# Temperature_monitoring.net
KiCad netlist of a schematic drawn in Altium Designer
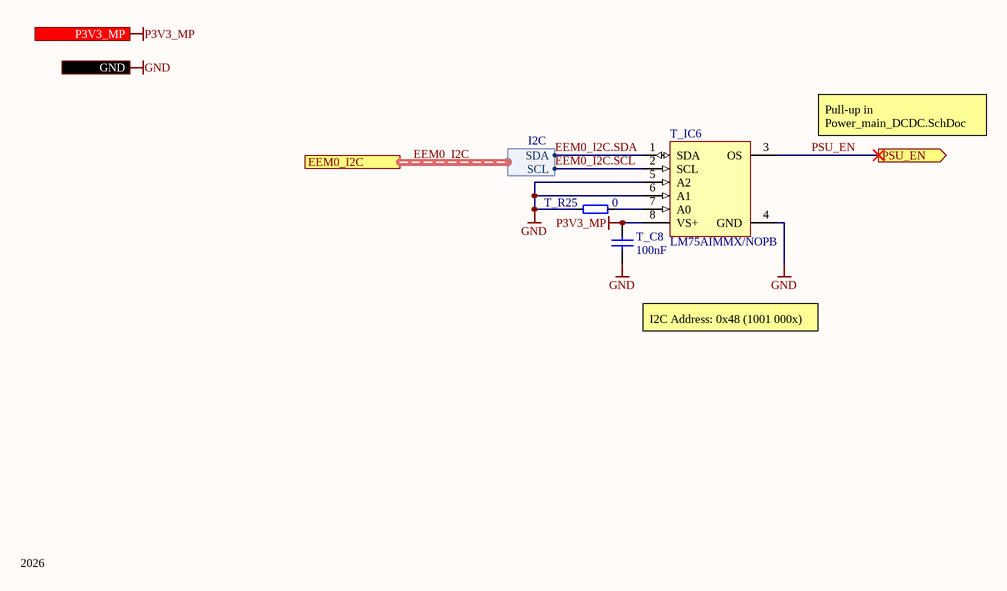
[diagram p0: Temperature_monitoring.SchDoc]

(export (version "E")
  (design (tool "Eeschema 10.0.6"))
  (components
    (comp (ref "T_C8")
      (value "100nF")
      (footprint "CAPC1005X55N")
      (description "Non-polarised capacitor")
      (fields
        (field (name "PART NUMBER") "CC0402_100NF_16V_10%_X5R")
        (field (name "VOLTAGE") "16V")
        (field (name "AUTHOR") "CERN DEM JLC")
      )
      (libsource (lib "Capacitors") (part "Capacitor - non polarized"))
    )
    (comp (ref "T_IC6")
      (value "LM75AIMMX/NOPB")
      (footprint "DGK0008A_M")
      (description "Serial Switch/Digital Sensor, 9 Bit(s), 3Cel, Square, 8 Pin, Surface Mount")
      (libsource (lib "TechnoSystem Workspace") (part "SEN-TEMP-LM75-8"))
    )
    (comp (ref "T_R25")
      (value "0")
      (footprint "RESC1005X40N")
      (description "Resistor")
      (fields
        (field (name "PART NUMBER") "R0402_0R_JUMPER")
        (field (name "MANUFACTURER") "GENERIC")
        (field (name "AUTHOR") "CERN DEM JLC")
      )
      (libsource (lib "Resistors") (part "Resistor"))
    )
  )
  (nets
    (net (code "2") (name "/EEM0_I2C.SCL") (class "Default")
      (node (ref "T_IC6") (pin "2") (pinfunction "SCL_2") (pintype "input"))
    )
    (net (code "3") (name "/EEM0_I2C.SDA") (class "Default")
      (node (ref "T_IC6") (pin "1") (pinfunction "SDA_1") (pintype "bidirectional"))
    )
    (net (code "5") (name "/PSU_EN") (class "Default")
      (node (ref "T_IC6") (pin "3") (pinfunction "OS_3") (pintype "open_collector+no_connect"))
    )
    (net (code "6") (name "GND") (class "Default")
      (node (ref "T_C8") (pin "1") (pinfunction "1_1") (pintype "passive"))
      (node (ref "T_IC6") (pin "4") (pinfunction "GND_4") (pintype "power_in"))
      (node (ref "T_IC6") (pin "5") (pinfunction "A2_5") (pintype "input"))
      (node (ref "T_IC6") (pin "6") (pinfunction "A1_6") (pintype "input"))
      (node (ref "T_R25") (pin "1") (pinfunction "1_1") (pintype "passive"))
    )
    (net (code "7") (name "Net-(T_IC6-A0)") (class "Default")
      (node (ref "T_IC6") (pin "7") (pinfunction "A0_7") (pintype "input"))
      (node (ref "T_R25") (pin "2") (pinfunction "2_2") (pintype "passive"))
    )
    (net (code "8") (name "P3V3_MP") (class "Default")
      (node (ref "T_C8") (pin "2") (pinfunction "2_2") (pintype "passive"))
      (node (ref "T_IC6") (pin "8") (pinfunction "VS+_8") (pintype "power_in"))
    )
  )
)
